# PT100RTD.net
KiCad netlist of a schematic drawn in EAGLE
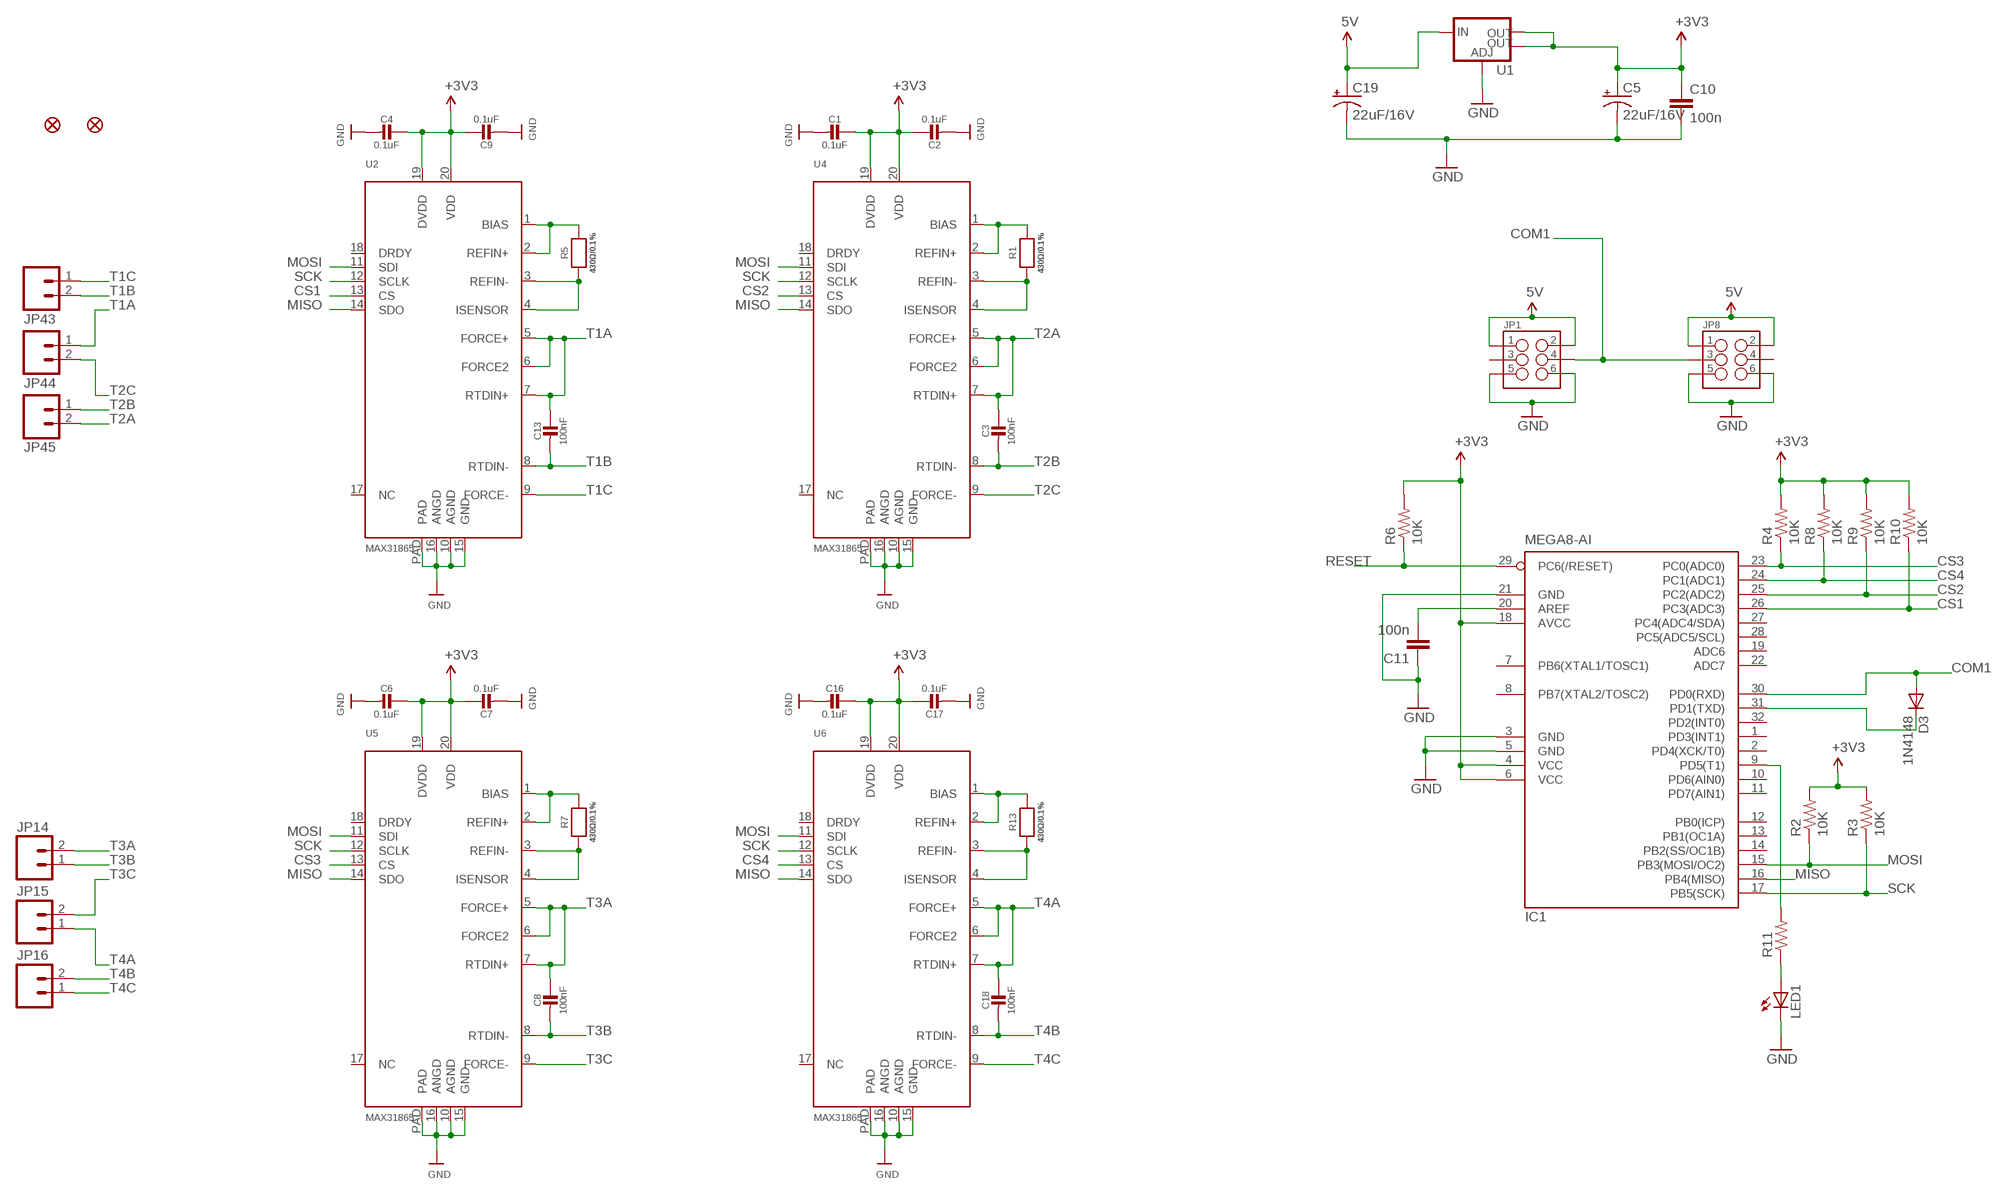
[diagram p0: schematic, sheet 1]

(export (version "E")
  (design (tool "Eeschema 10.0.6"))
  (components
    (comp (ref "C1")
      (value "0.1uF")
      (footprint "eagle-import:0805-NO")
      (libsource (lib "eagle-import") (part "CAP_CERAMIC0805-NOOUTLINE"))
    )
    (comp (ref "C2")
      (value "0.1uF")
      (footprint "eagle-import:0805-NO")
      (libsource (lib "eagle-import") (part "CAP_CERAMIC0805-NOOUTLINE"))
    )
    (comp (ref "C3")
      (value "100nF")
      (footprint "eagle-import:0805-NO")
      (libsource (lib "eagle-import") (part "CAP_CERAMIC0805-NOOUTLINE"))
    )
    (comp (ref "C4")
      (value "0.1uF")
      (footprint "eagle-import:0805-NO")
      (libsource (lib "eagle-import") (part "CAP_CERAMIC0805-NOOUTLINE"))
    )
    (comp (ref "C5")
      (value "22uF/16V")
      (footprint "eagle-import:EIA3216")
      (libsource (lib "eagle-import") (part "CAP_POL1206"))
    )
    (comp (ref "C6")
      (value "0.1uF")
      (footprint "eagle-import:0805-NO")
      (libsource (lib "eagle-import") (part "CAP_CERAMIC0805-NOOUTLINE"))
    )
    (comp (ref "C7")
      (value "0.1uF")
      (footprint "eagle-import:0805-NO")
      (libsource (lib "eagle-import") (part "CAP_CERAMIC0805-NOOUTLINE"))
    )
    (comp (ref "C8")
      (value "100nF")
      (footprint "eagle-import:0805-NO")
      (libsource (lib "eagle-import") (part "CAP_CERAMIC0805-NOOUTLINE"))
    )
    (comp (ref "C9")
      (value "0.1uF")
      (footprint "eagle-import:0805-NO")
      (libsource (lib "eagle-import") (part "CAP_CERAMIC0805-NOOUTLINE"))
    )
    (comp (ref "C10")
      (value "100n")
      (footprint "eagle-import:0805")
      (libsource (lib "eagle-import") (part "CAP0805"))
    )
    (comp (ref "C11")
      (value "100n")
      (footprint "eagle-import:0805")
      (libsource (lib "eagle-import") (part "CAP0805"))
    )
    (comp (ref "C13")
      (value "100nF")
      (footprint "eagle-import:0805-NO")
      (libsource (lib "eagle-import") (part "CAP_CERAMIC0805-NOOUTLINE"))
    )
    (comp (ref "C16")
      (value "0.1uF")
      (footprint "eagle-import:0805-NO")
      (libsource (lib "eagle-import") (part "CAP_CERAMIC0805-NOOUTLINE"))
    )
    (comp (ref "C17")
      (value "0.1uF")
      (footprint "eagle-import:0805-NO")
      (libsource (lib "eagle-import") (part "CAP_CERAMIC0805-NOOUTLINE"))
    )
    (comp (ref "C18")
      (value "100nF")
      (footprint "eagle-import:0805-NO")
      (libsource (lib "eagle-import") (part "CAP_CERAMIC0805-NOOUTLINE"))
    )
    (comp (ref "C19")
      (value "22uF/16V")
      (footprint "eagle-import:EIA3216")
      (libsource (lib "eagle-import") (part "CAP_POL1206"))
    )
    (comp (ref "D3")
      (value "1N4148")
      (footprint "eagle-import:MINIMELF")
      (libsource (lib "eagle-import") (part "DIODE-MINIMELF"))
    )
    (comp (ref "FD1")
      (value "FIDUCIALUFIDUCIAL")
      (footprint "eagle-import:FIDUCIAL-MICRO")
      (libsource (lib "eagle-import") (part "FIDUCIALUFIDUCIAL"))
    )
    (comp (ref "FD2")
      (value "FIDUCIALUFIDUCIAL")
      (footprint "eagle-import:FIDUCIAL-MICRO")
      (libsource (lib "eagle-import") (part "FIDUCIALUFIDUCIAL"))
    )
    (comp (ref "IC1")
      (value "MEGA8-AI")
      (footprint "eagle-import:TQFP32-08")
      (fields (field (name "MPN") "ATMEGA8-16AU"))
      (libsource (lib "eagle-import") (part "MEGA8-AI"))
    )
    (comp (ref "JP1")
      (value "M03X22X3_SILK_MALE_PTH")
      (footprint "eagle-import:2X3")
      (libsource (lib "eagle-import") (part "M03X22X3_SILK_MALE_PTH"))
    )
    (comp (ref "JP8")
      (value "M03X22X3_SILK_MALE_PTH")
      (footprint "eagle-import:2X3")
      (libsource (lib "eagle-import") (part "M03X22X3_SILK_MALE_PTH"))
    )
    (comp (ref "JP14")
      (value "M025MM")
      (footprint "eagle-import:SCREWTERMINAL-5MM-2")
      (libsource (lib "eagle-import") (part "M025MM"))
    )
    (comp (ref "JP15")
      (value "M025MM")
      (footprint "eagle-import:SCREWTERMINAL-5MM-2")
      (libsource (lib "eagle-import") (part "M025MM"))
    )
    (comp (ref "JP16")
      (value "M025MM")
      (footprint "eagle-import:SCREWTERMINAL-5MM-2")
      (libsource (lib "eagle-import") (part "M025MM"))
    )
    (comp (ref "JP43")
      (value "M025MM")
      (footprint "eagle-import:SCREWTERMINAL-5MM-2")
      (libsource (lib "eagle-import") (part "M025MM"))
    )
    (comp (ref "JP44")
      (value "M025MM")
      (footprint "eagle-import:SCREWTERMINAL-5MM-2")
      (libsource (lib "eagle-import") (part "M025MM"))
    )
    (comp (ref "JP45")
      (value "M025MM")
      (footprint "eagle-import:SCREWTERMINAL-5MM-2")
      (libsource (lib "eagle-import") (part "M025MM"))
    )
    (comp (ref "LED1")
      (value "LEDCHIP-LED0805")
      (footprint "eagle-import:CHIP-LED0805")
      (libsource (lib "eagle-import") (part "LEDCHIP-LED0805"))
    )
    (comp (ref "R1")
      (value "430Ω/0.1%")
      (footprint "eagle-import:0805-NO")
      (libsource (lib "eagle-import") (part "RESISTOR0805_NOOUTLINE"))
    )
    (comp (ref "R2")
      (value "10K")
      (footprint "eagle-import:0805")
      (libsource (lib "eagle-import") (part "RESISTOR0805-RES"))
    )
    (comp (ref "R3")
      (value "10K")
      (footprint "eagle-import:0805")
      (libsource (lib "eagle-import") (part "RESISTOR0805-RES"))
    )
    (comp (ref "R4")
      (value "10K")
      (footprint "eagle-import:0805")
      (libsource (lib "eagle-import") (part "RESISTOR0805-RES"))
    )
    (comp (ref "R5")
      (value "430Ω/0.1%")
      (footprint "eagle-import:0805-NO")
      (libsource (lib "eagle-import") (part "RESISTOR0805_NOOUTLINE"))
    )
    (comp (ref "R6")
      (value "10K")
      (footprint "eagle-import:0805")
      (libsource (lib "eagle-import") (part "RESISTOR0805-RES"))
    )
    (comp (ref "R7")
      (value "430Ω/0.1%")
      (footprint "eagle-import:0805-NO")
      (libsource (lib "eagle-import") (part "RESISTOR0805_NOOUTLINE"))
    )
    (comp (ref "R8")
      (value "10K")
      (footprint "eagle-import:0805")
      (libsource (lib "eagle-import") (part "RESISTOR0805-RES"))
    )
    (comp (ref "R9")
      (value "10K")
      (footprint "eagle-import:0805")
      (libsource (lib "eagle-import") (part "RESISTOR0805-RES"))
    )
    (comp (ref "R10")
      (value "10K")
      (footprint "eagle-import:0805")
      (libsource (lib "eagle-import") (part "RESISTOR0805-RES"))
    )
    (comp (ref "R11")
      (value "RESISTOR0805-RES")
      (footprint "eagle-import:0805")
      (libsource (lib "eagle-import") (part "RESISTOR0805-RES"))
    )
    (comp (ref "R13")
      (value "430Ω/0.1%")
      (footprint "eagle-import:0805-NO")
      (libsource (lib "eagle-import") (part "RESISTOR0805_NOOUTLINE"))
    )
    (comp (ref "U1")
      (value "V_REG_LM1117SOT223")
      (footprint "eagle-import:SOT223")
      (libsource (lib "eagle-import") (part "V_REG_LM1117SOT223"))
    )
    (comp (ref "U2")
      (value "MAX31865")
      (footprint "eagle-import:QFN20_4MM_0.65MM")
      (libsource (lib "eagle-import") (part "TEMP_MAX31865"))
    )
    (comp (ref "U4")
      (value "MAX31865")
      (footprint "eagle-import:QFN20_4MM_0.65MM")
      (libsource (lib "eagle-import") (part "TEMP_MAX31865"))
    )
    (comp (ref "U5")
      (value "MAX31865")
      (footprint "eagle-import:QFN20_4MM_0.65MM")
      (libsource (lib "eagle-import") (part "TEMP_MAX31865"))
    )
    (comp (ref "U6")
      (value "MAX31865")
      (footprint "eagle-import:QFN20_4MM_0.65MM")
      (libsource (lib "eagle-import") (part "TEMP_MAX31865"))
    )
  )
  (nets
    (net (code "1") (name "+3V3") (class "Default")
      (node (ref "C1") (pin "1") (pinfunction "1_1") (pintype "passive"))
      (node (ref "C10") (pin "1") (pinfunction "1_1") (pintype "passive"))
      (node (ref "C16") (pin "1") (pinfunction "1_1") (pintype "passive"))
      (node (ref "C17") (pin "1") (pinfunction "1_1") (pintype "passive"))
      (node (ref "C2") (pin "1") (pinfunction "1_1") (pintype "passive"))
      (node (ref "C4") (pin "1") (pinfunction "1_1") (pintype "passive"))
      (node (ref "C5") (pin "A") (pinfunction "+_A") (pintype "passive"))
      (node (ref "C6") (pin "1") (pinfunction "1_1") (pintype "passive"))
      (node (ref "C7") (pin "1") (pinfunction "1_1") (pintype "passive"))
      (node (ref "C9") (pin "1") (pinfunction "1_1") (pintype "passive"))
      (node (ref "IC1") (pin "18") (pinfunction "AVCC_18") (pintype "power_in"))
      (node (ref "IC1") (pin "4") (pinfunction "VCC_4") (pintype "power_in"))
      (node (ref "IC1") (pin "6") (pinfunction "VCC_6") (pintype "power_in"))
      (node (ref "R10") (pin "2") (pinfunction "2_2") (pintype "passive"))
      (node (ref "R2") (pin "2") (pinfunction "2_2") (pintype "passive"))
      (node (ref "R3") (pin "2") (pinfunction "2_2") (pintype "passive"))
      (node (ref "R4") (pin "2") (pinfunction "2_2") (pintype "passive"))
      (node (ref "R6") (pin "2") (pinfunction "2_2") (pintype "passive"))
      (node (ref "R8") (pin "2") (pinfunction "2_2") (pintype "passive"))
      (node (ref "R9") (pin "2") (pinfunction "2_2") (pintype "passive"))
      (node (ref "U1") (pin "2") (pinfunction "OUT_2") (pintype "output"))
      (node (ref "U1") (pin "4") (pinfunction "OUT_4") (pintype "output"))
      (node (ref "U2") (pin "19") (pinfunction "DVDD_19") (pintype "power_in"))
      (node (ref "U2") (pin "20") (pinfunction "VDD_20") (pintype "power_in"))
      (node (ref "U4") (pin "19") (pinfunction "DVDD_19") (pintype "power_in"))
      (node (ref "U4") (pin "20") (pinfunction "VDD_20") (pintype "power_in"))
      (node (ref "U5") (pin "19") (pinfunction "DVDD_19") (pintype "power_in"))
      (node (ref "U5") (pin "20") (pinfunction "VDD_20") (pintype "power_in"))
      (node (ref "U6") (pin "19") (pinfunction "DVDD_19") (pintype "power_in"))
      (node (ref "U6") (pin "20") (pinfunction "VDD_20") (pintype "power_in"))
    )
    (net (code "2") (name "/COM1") (class "Default")
      (node (ref "D3") (pin "A") (pinfunction "A_A") (pintype "passive"))
      (node (ref "IC1") (pin "30") (pinfunction "PD0(RXD)_30") (pintype "bidirectional"))
      (node (ref "JP1") (pin "4") (pinfunction "4_4") (pintype "bidirectional"))
      (node (ref "JP8") (pin "3") (pinfunction "3_3") (pintype "bidirectional"))
    )
    (net (code "3") (name "/CS1") (class "Default")
      (node (ref "IC1") (pin "26") (pinfunction "PC3(ADC3)_26") (pintype "bidirectional"))
      (node (ref "R10") (pin "1") (pinfunction "1_1") (pintype "passive"))
      (node (ref "U2") (pin "13") (pinfunction "CS_13") (pintype "input"))
    )
    (net (code "4") (name "/CS2") (class "Default")
      (node (ref "IC1") (pin "25") (pinfunction "PC2(ADC2)_25") (pintype "bidirectional"))
      (node (ref "R9") (pin "1") (pinfunction "1_1") (pintype "passive"))
      (node (ref "U4") (pin "13") (pinfunction "CS_13") (pintype "input"))
    )
    (net (code "5") (name "/CS3") (class "Default")
      (node (ref "IC1") (pin "23") (pinfunction "PC0(ADC0)_23") (pintype "bidirectional"))
      (node (ref "R4") (pin "1") (pinfunction "1_1") (pintype "passive"))
      (node (ref "U5") (pin "13") (pinfunction "CS_13") (pintype "input"))
    )
    (net (code "6") (name "/CS4") (class "Default")
      (node (ref "IC1") (pin "24") (pinfunction "PC1(ADC1)_24") (pintype "bidirectional"))
      (node (ref "R8") (pin "1") (pinfunction "1_1") (pintype "passive"))
      (node (ref "U6") (pin "13") (pinfunction "CS_13") (pintype "input"))
    )
    (net (code "7") (name "/MISO") (class "Default")
      (node (ref "IC1") (pin "16") (pinfunction "PB4(MISO)_16") (pintype "bidirectional"))
      (node (ref "U2") (pin "14") (pinfunction "SDO_14") (pintype "output"))
      (node (ref "U4") (pin "14") (pinfunction "SDO_14") (pintype "output"))
      (node (ref "U5") (pin "14") (pinfunction "SDO_14") (pintype "output"))
      (node (ref "U6") (pin "14") (pinfunction "SDO_14") (pintype "output"))
    )
    (net (code "8") (name "/MOSI") (class "Default")
      (node (ref "IC1") (pin "15") (pinfunction "PB3(MOSI/OC2)_15") (pintype "bidirectional"))
      (node (ref "R2") (pin "1") (pinfunction "1_1") (pintype "passive"))
      (node (ref "U2") (pin "11") (pinfunction "SDI_11") (pintype "input"))
      (node (ref "U4") (pin "11") (pinfunction "SDI_11") (pintype "input"))
      (node (ref "U5") (pin "11") (pinfunction "SDI_11") (pintype "input"))
      (node (ref "U6") (pin "11") (pinfunction "SDI_11") (pintype "input"))
    )
    (net (code "9") (name "/RESET") (class "Default")
      (node (ref "IC1") (pin "29") (pinfunction "PC6(/RESET)_29") (pintype "bidirectional"))
      (node (ref "R6") (pin "1") (pinfunction "1_1") (pintype "passive"))
    )
    (net (code "10") (name "/SCK") (class "Default")
      (node (ref "IC1") (pin "17") (pinfunction "PB5(SCK)_17") (pintype "bidirectional"))
      (node (ref "R3") (pin "1") (pinfunction "1_1") (pintype "passive"))
      (node (ref "U2") (pin "12") (pinfunction "SCLK_12") (pintype "input"))
      (node (ref "U4") (pin "12") (pinfunction "SCLK_12") (pintype "input"))
      (node (ref "U5") (pin "12") (pinfunction "SCLK_12") (pintype "input"))
      (node (ref "U6") (pin "12") (pinfunction "SCLK_12") (pintype "input"))
    )
    (net (code "11") (name "/T1A") (class "Default")
      (node (ref "C13") (pin "1") (pinfunction "1_1") (pintype "passive"))
      (node (ref "JP44") (pin "1") (pinfunction "1_1") (pintype "passive"))
      (node (ref "U2") (pin "5") (pinfunction "FORCE+_5") (pintype "output"))
      (node (ref "U2") (pin "6") (pinfunction "FORCE2_6") (pintype "bidirectional"))
      (node (ref "U2") (pin "7") (pinfunction "RTDIN+_7") (pintype "bidirectional"))
    )
    (net (code "12") (name "/T1B") (class "Default")
      (node (ref "C13") (pin "2") (pinfunction "2_2") (pintype "passive"))
      (node (ref "JP43") (pin "2") (pinfunction "2_2") (pintype "passive"))
      (node (ref "U2") (pin "8") (pinfunction "RTDIN-_8") (pintype "bidirectional"))
    )
    (net (code "13") (name "/T1C") (class "Default")
      (node (ref "JP43") (pin "1") (pinfunction "1_1") (pintype "passive"))
      (node (ref "U2") (pin "9") (pinfunction "FORCE-_9") (pintype "input"))
    )
    (net (code "14") (name "/T2A") (class "Default")
      (node (ref "C3") (pin "1") (pinfunction "1_1") (pintype "passive"))
      (node (ref "JP45") (pin "2") (pinfunction "2_2") (pintype "passive"))
      (node (ref "U4") (pin "5") (pinfunction "FORCE+_5") (pintype "output"))
      (node (ref "U4") (pin "6") (pinfunction "FORCE2_6") (pintype "bidirectional"))
      (node (ref "U4") (pin "7") (pinfunction "RTDIN+_7") (pintype "bidirectional"))
    )
    (net (code "15") (name "/T2B") (class "Default")
      (node (ref "C3") (pin "2") (pinfunction "2_2") (pintype "passive"))
      (node (ref "JP45") (pin "1") (pinfunction "1_1") (pintype "passive"))
      (node (ref "U4") (pin "8") (pinfunction "RTDIN-_8") (pintype "bidirectional"))
    )
    (net (code "16") (name "/T2C") (class "Default")
      (node (ref "JP44") (pin "2") (pinfunction "2_2") (pintype "passive"))
      (node (ref "U4") (pin "9") (pinfunction "FORCE-_9") (pintype "input"))
    )
    (net (code "17") (name "/T3A") (class "Default")
      (node (ref "C8") (pin "1") (pinfunction "1_1") (pintype "passive"))
      (node (ref "JP14") (pin "2") (pinfunction "2_2") (pintype "passive"))
      (node (ref "U5") (pin "5") (pinfunction "FORCE+_5") (pintype "output"))
      (node (ref "U5") (pin "6") (pinfunction "FORCE2_6") (pintype "bidirectional"))
      (node (ref "U5") (pin "7") (pinfunction "RTDIN+_7") (pintype "bidirectional"))
    )
    (net (code "18") (name "/T3B") (class "Default")
      (node (ref "C8") (pin "2") (pinfunction "2_2") (pintype "passive"))
      (node (ref "JP14") (pin "1") (pinfunction "1_1") (pintype "passive"))
      (node (ref "U5") (pin "8") (pinfunction "RTDIN-_8") (pintype "bidirectional"))
    )
    (net (code "19") (name "/T3C") (class "Default")
      (node (ref "JP15") (pin "2") (pinfunction "2_2") (pintype "passive"))
      (node (ref "U5") (pin "9") (pinfunction "FORCE-_9") (pintype "input"))
    )
    (net (code "20") (name "/T4A") (class "Default")
      (node (ref "C18") (pin "1") (pinfunction "1_1") (pintype "passive"))
      (node (ref "JP15") (pin "1") (pinfunction "1_1") (pintype "passive"))
      (node (ref "U6") (pin "5") (pinfunction "FORCE+_5") (pintype "output"))
      (node (ref "U6") (pin "6") (pinfunction "FORCE2_6") (pintype "bidirectional"))
      (node (ref "U6") (pin "7") (pinfunction "RTDIN+_7") (pintype "bidirectional"))
    )
    (net (code "21") (name "/T4B") (class "Default")
      (node (ref "C18") (pin "2") (pinfunction "2_2") (pintype "passive"))
      (node (ref "JP16") (pin "2") (pinfunction "2_2") (pintype "passive"))
      (node (ref "U6") (pin "8") (pinfunction "RTDIN-_8") (pintype "bidirectional"))
    )
    (net (code "22") (name "/T4C") (class "Default")
      (node (ref "JP16") (pin "1") (pinfunction "1_1") (pintype "passive"))
      (node (ref "U6") (pin "9") (pinfunction "FORCE-_9") (pintype "input"))
    )
    (net (code "23") (name "5V") (class "Default")
      (node (ref "C19") (pin "A") (pinfunction "+_A") (pintype "passive"))
      (node (ref "JP1") (pin "1") (pinfunction "1_1") (pintype "bidirectional"))
      (node (ref "JP1") (pin "2") (pinfunction "2_2") (pintype "bidirectional"))
      (node (ref "JP8") (pin "1") (pinfunction "1_1") (pintype "bidirectional"))
      (node (ref "JP8") (pin "2") (pinfunction "2_2") (pintype "bidirectional"))
      (node (ref "U1") (pin "3") (pinfunction "IN_3") (pintype "input"))
    )
    (net (code "24") (name "GND") (class "Default")
      (node (ref "C1") (pin "2") (pinfunction "2_2") (pintype "passive"))
      (node (ref "C10") (pin "2") (pinfunction "2_2") (pintype "passive"))
      (node (ref "C11") (pin "1") (pinfunction "1_1") (pintype "passive"))
      (node (ref "C16") (pin "2") (pinfunction "2_2") (pintype "passive"))
      (node (ref "C17") (pin "2") (pinfunction "2_2") (pintype "passive"))
      (node (ref "C19") (pin "C") (pinfunction "-_C") (pintype "passive"))
      (node (ref "C2") (pin "2") (pinfunction "2_2") (pintype "passive"))
      (node (ref "C4") (pin "2") (pinfunction "2_2") (pintype "passive"))
      (node (ref "C5") (pin "C") (pinfunction "-_C") (pintype "passive"))
      (node (ref "C6") (pin "2") (pinfunction "2_2") (pintype "passive"))
      (node (ref "C7") (pin "2") (pinfunction "2_2") (pintype "passive"))
      (node (ref "C9") (pin "2") (pinfunction "2_2") (pintype "passive"))
      (node (ref "IC1") (pin "21") (pinfunction "GND_21") (pintype "power_in"))
      (node (ref "IC1") (pin "3") (pinfunction "GND_3") (pintype "power_in"))
      (node (ref "IC1") (pin "5") (pinfunction "GND_5") (pintype "power_in"))
      (node (ref "JP1") (pin "5") (pinfunction "5_5") (pintype "bidirectional"))
      (node (ref "JP1") (pin "6") (pinfunction "6_6") (pintype "bidirectional"))
      (node (ref "JP8") (pin "5") (pinfunction "5_5") (pintype "bidirectional"))
      (node (ref "JP8") (pin "6") (pinfunction "6_6") (pintype "bidirectional"))
      (node (ref "LED1") (pin "C") (pinfunction "C_C") (pintype "passive"))
      (node (ref "U1") (pin "1") (pinfunction "ADJ_1") (pintype "input"))
      (node (ref "U2") (pin "10") (pinfunction "AGND_10") (pintype "power_in"))
      (node (ref "U2") (pin "15") (pinfunction "GND_15") (pintype "power_in"))
      (node (ref "U2") (pin "16") (pinfunction "ANGD_16") (pintype "power_in"))
      (node (ref "U2") (pin "PAD") (pinfunction "PAD_PAD") (pintype "power_in"))
      (node (ref "U4") (pin "10") (pinfunction "AGND_10") (pintype "power_in"))
      (node (ref "U4") (pin "15") (pinfunction "GND_15") (pintype "power_in"))
      (node (ref "U4") (pin "16") (pinfunction "ANGD_16") (pintype "power_in"))
      (node (ref "U4") (pin "PAD") (pinfunction "PAD_PAD") (pintype "power_in"))
      (node (ref "U5") (pin "10") (pinfunction "AGND_10") (pintype "power_in"))
      (node (ref "U5") (pin "15") (pinfunction "GND_15") (pintype "power_in"))
      (node (ref "U5") (pin "16") (pinfunction "ANGD_16") (pintype "power_in"))
      (node (ref "U5") (pin "PAD") (pinfunction "PAD_PAD") (pintype "power_in"))
      (node (ref "U6") (pin "10") (pinfunction "AGND_10") (pintype "power_in"))
      (node (ref "U6") (pin "15") (pinfunction "GND_15") (pintype "power_in"))
      (node (ref "U6") (pin "16") (pinfunction "ANGD_16") (pintype "power_in"))
      (node (ref "U6") (pin "PAD") (pinfunction "PAD_PAD") (pintype "power_in"))
    )
    (net (code "25") (name "Net-(IC1-AREF)") (class "Default")
      (node (ref "C11") (pin "2") (pinfunction "2_2") (pintype "passive"))
      (node (ref "IC1") (pin "20") (pinfunction "AREF_20") (pintype "passive"))
    )
    (net (code "26") (name "Net-(IC1-PD1(TXD))") (class "Default")
      (node (ref "D3") (pin "C") (pinfunction "C_C") (pintype "passive"))
      (node (ref "IC1") (pin "31") (pinfunction "PD1(TXD)_31") (pintype "bidirectional"))
    )
    (net (code "27") (name "Net-(IC1-PD5(T1))") (class "Default")
      (node (ref "IC1") (pin "9") (pinfunction "PD5(T1)_9") (pintype "bidirectional"))
      (node (ref "R11") (pin "2") (pinfunction "2_2") (pintype "passive"))
    )
    (net (code "28") (name "Net-(LED1-PadA)") (class "Default")
      (node (ref "LED1") (pin "A") (pinfunction "A_A") (pintype "passive"))
      (node (ref "R11") (pin "1") (pinfunction "1_1") (pintype "passive"))
    )
    (net (code "29") (name "Net-(U2-BIAS)") (class "Default")
      (node (ref "R5") (pin "2") (pinfunction "2_2") (pintype "passive"))
      (node (ref "U2") (pin "1") (pinfunction "BIAS_1") (pintype "output"))
      (node (ref "U2") (pin "2") (pinfunction "REFIN+_2") (pintype "bidirectional"))
    )
    (net (code "30") (name "Net-(U2-ISENSOR)") (class "Default")
      (node (ref "R5") (pin "1") (pinfunction "1_1") (pintype "passive"))
      (node (ref "U2") (pin "3") (pinfunction "REFIN-_3") (pintype "bidirectional"))
      (node (ref "U2") (pin "4") (pinfunction "ISENSOR_4") (pintype "input"))
    )
    (net (code "31") (name "Net-(U4-BIAS)") (class "Default")
      (node (ref "R1") (pin "2") (pinfunction "2_2") (pintype "passive"))
      (node (ref "U4") (pin "1") (pinfunction "BIAS_1") (pintype "output"))
      (node (ref "U4") (pin "2") (pinfunction "REFIN+_2") (pintype "bidirectional"))
    )
    (net (code "32") (name "Net-(U4-ISENSOR)") (class "Default")
      (node (ref "R1") (pin "1") (pinfunction "1_1") (pintype "passive"))
      (node (ref "U4") (pin "3") (pinfunction "REFIN-_3") (pintype "bidirectional"))
      (node (ref "U4") (pin "4") (pinfunction "ISENSOR_4") (pintype "input"))
    )
    (net (code "33") (name "Net-(U5-BIAS)") (class "Default")
      (node (ref "R7") (pin "2") (pinfunction "2_2") (pintype "passive"))
      (node (ref "U5") (pin "1") (pinfunction "BIAS_1") (pintype "output"))
      (node (ref "U5") (pin "2") (pinfunction "REFIN+_2") (pintype "bidirectional"))
    )
    (net (code "34") (name "Net-(U5-ISENSOR)") (class "Default")
      (node (ref "R7") (pin "1") (pinfunction "1_1") (pintype "passive"))
      (node (ref "U5") (pin "3") (pinfunction "REFIN-_3") (pintype "bidirectional"))
      (node (ref "U5") (pin "4") (pinfunction "ISENSOR_4") (pintype "input"))
    )
    (net (code "35") (name "Net-(U6-BIAS)") (class "Default")
      (node (ref "R13") (pin "2") (pinfunction "2_2") (pintype "passive"))
      (node (ref "U6") (pin "1") (pinfunction "BIAS_1") (pintype "output"))
      (node (ref "U6") (pin "2") (pinfunction "REFIN+_2") (pintype "bidirectional"))
    )
    (net (code "36") (name "Net-(U6-ISENSOR)") (class "Default")
      (node (ref "R13") (pin "1") (pinfunction "1_1") (pintype "passive"))
      (node (ref "U6") (pin "3") (pinfunction "REFIN-_3") (pintype "bidirectional"))
      (node (ref "U6") (pin "4") (pinfunction "ISENSOR_4") (pintype "input"))
    )
    (net (code "37") (name "unconnected-(IC1-ADC6-Pad19)") (class "Default")
      (node (ref "IC1") (pin "19") (pinfunction "ADC6_19") (pintype "bidirectional"))
    )
    (net (code "38") (name "unconnected-(IC1-ADC7-Pad22)") (class "Default")
      (node (ref "IC1") (pin "22") (pinfunction "ADC7_22") (pintype "bidirectional"))
    )
    (net (code "39") (name "unconnected-(IC1-PB0(ICP)-Pad12)") (class "Default")
      (node (ref "IC1") (pin "12") (pinfunction "PB0(ICP)_12") (pintype "bidirectional"))
    )
    (net (code "40") (name "unconnected-(IC1-PB1(OC1A)-Pad13)") (class "Default")
      (node (ref "IC1") (pin "13") (pinfunction "PB1(OC1A)_13") (pintype "bidirectional"))
    )
    (net (code "41") (name "unconnected-(IC1-PB2(SS{slash}OC1B)-Pad14)") (class "Default")
      (node (ref "IC1") (pin "14") (pinfunction "PB2(SS/OC1B)_14") (pintype "bidirectional"))
    )
    (net (code "42") (name "unconnected-(IC1-PB6(XTAL1{slash}TOSC1)-Pad7)") (class "Default")
      (node (ref "IC1") (pin "7") (pinfunction "PB6(XTAL1/TOSC1)_7") (pintype "bidirectional"))
    )
    (net (code "43") (name "unconnected-(IC1-PB7(XTAL2{slash}TOSC2)-Pad8)") (class "Default")
      (node (ref "IC1") (pin "8") (pinfunction "PB7(XTAL2/TOSC2)_8") (pintype "bidirectional"))
    )
    (net (code "44") (name "unconnected-(IC1-PC4(ADC4{slash}SDA)-Pad27)") (class "Default")
      (node (ref "IC1") (pin "27") (pinfunction "PC4(ADC4/SDA)_27") (pintype "bidirectional"))
    )
    (net (code "45") (name "unconnected-(IC1-PC5(ADC5{slash}SCL)-Pad28)") (class "Default")
      (node (ref "IC1") (pin "28") (pinfunction "PC5(ADC5/SCL)_28") (pintype "bidirectional"))
    )
    (net (code "46") (name "unconnected-(IC1-PD2(INT0)-Pad32)") (class "Default")
      (node (ref "IC1") (pin "32") (pinfunction "PD2(INT0)_32") (pintype "bidirectional"))
    )
    (net (code "47") (name "unconnected-(IC1-PD3(INT1)-Pad1)") (class "Default")
      (node (ref "IC1") (pin "1") (pinfunction "PD3(INT1)_1") (pintype "bidirectional"))
    )
    (net (code "48") (name "unconnected-(IC1-PD4(XCK{slash}T0)-Pad2)") (class "Default")
      (node (ref "IC1") (pin "2") (pinfunction "PD4(XCK/T0)_2") (pintype "bidirectional"))
    )
    (net (code "49") (name "unconnected-(IC1-PD6(AIN0)-Pad10)") (class "Default")
      (node (ref "IC1") (pin "10") (pinfunction "PD6(AIN0)_10") (pintype "bidirectional"))
    )
    (net (code "50") (name "unconnected-(IC1-PD7(AIN1)-Pad11)") (class "Default")
      (node (ref "IC1") (pin "11") (pinfunction "PD7(AIN1)_11") (pintype "bidirectional"))
    )
    (net (code "51") (name "unconnected-(JP1-Pad3)") (class "Default")
      (node (ref "JP1") (pin "3") (pinfunction "3_3") (pintype "bidirectional"))
    )
    (net (code "52") (name "unconnected-(JP8-Pad4)") (class "Default")
      (node (ref "JP8") (pin "4") (pinfunction "4_4") (pintype "bidirectional"))
    )
    (net (code "53") (name "unconnected-(U2-DRDY-Pad18)") (class "Default")
      (node (ref "U2") (pin "18") (pinfunction "DRDY_18") (pintype "output"))
    )
    (net (code "54") (name "unconnected-(U2-NC-Pad17)") (class "Default")
      (node (ref "U2") (pin "17") (pinfunction "NC_17") (pintype "no_connect"))
    )
    (net (code "55") (name "unconnected-(U4-DRDY-Pad18)") (class "Default")
      (node (ref "U4") (pin "18") (pinfunction "DRDY_18") (pintype "output"))
    )
    (net (code "56") (name "unconnected-(U4-NC-Pad17)") (class "Default")
      (node (ref "U4") (pin "17") (pinfunction "NC_17") (pintype "no_connect"))
    )
    (net (code "57") (name "unconnected-(U5-DRDY-Pad18)") (class "Default")
      (node (ref "U5") (pin "18") (pinfunction "DRDY_18") (pintype "output"))
    )
    (net (code "58") (name "unconnected-(U5-NC-Pad17)") (class "Default")
      (node (ref "U5") (pin "17") (pinfunction "NC_17") (pintype "no_connect"))
    )
    (net (code "59") (name "unconnected-(U6-DRDY-Pad18)") (class "Default")
      (node (ref "U6") (pin "18") (pinfunction "DRDY_18") (pintype "output"))
    )
    (net (code "60") (name "unconnected-(U6-NC-Pad17)") (class "Default")
      (node (ref "U6") (pin "17") (pinfunction "NC_17") (pintype "no_connect"))
    )
  )
)
